# p1dc-001.net
KiCad netlist of a schematic drawn in EAGLE
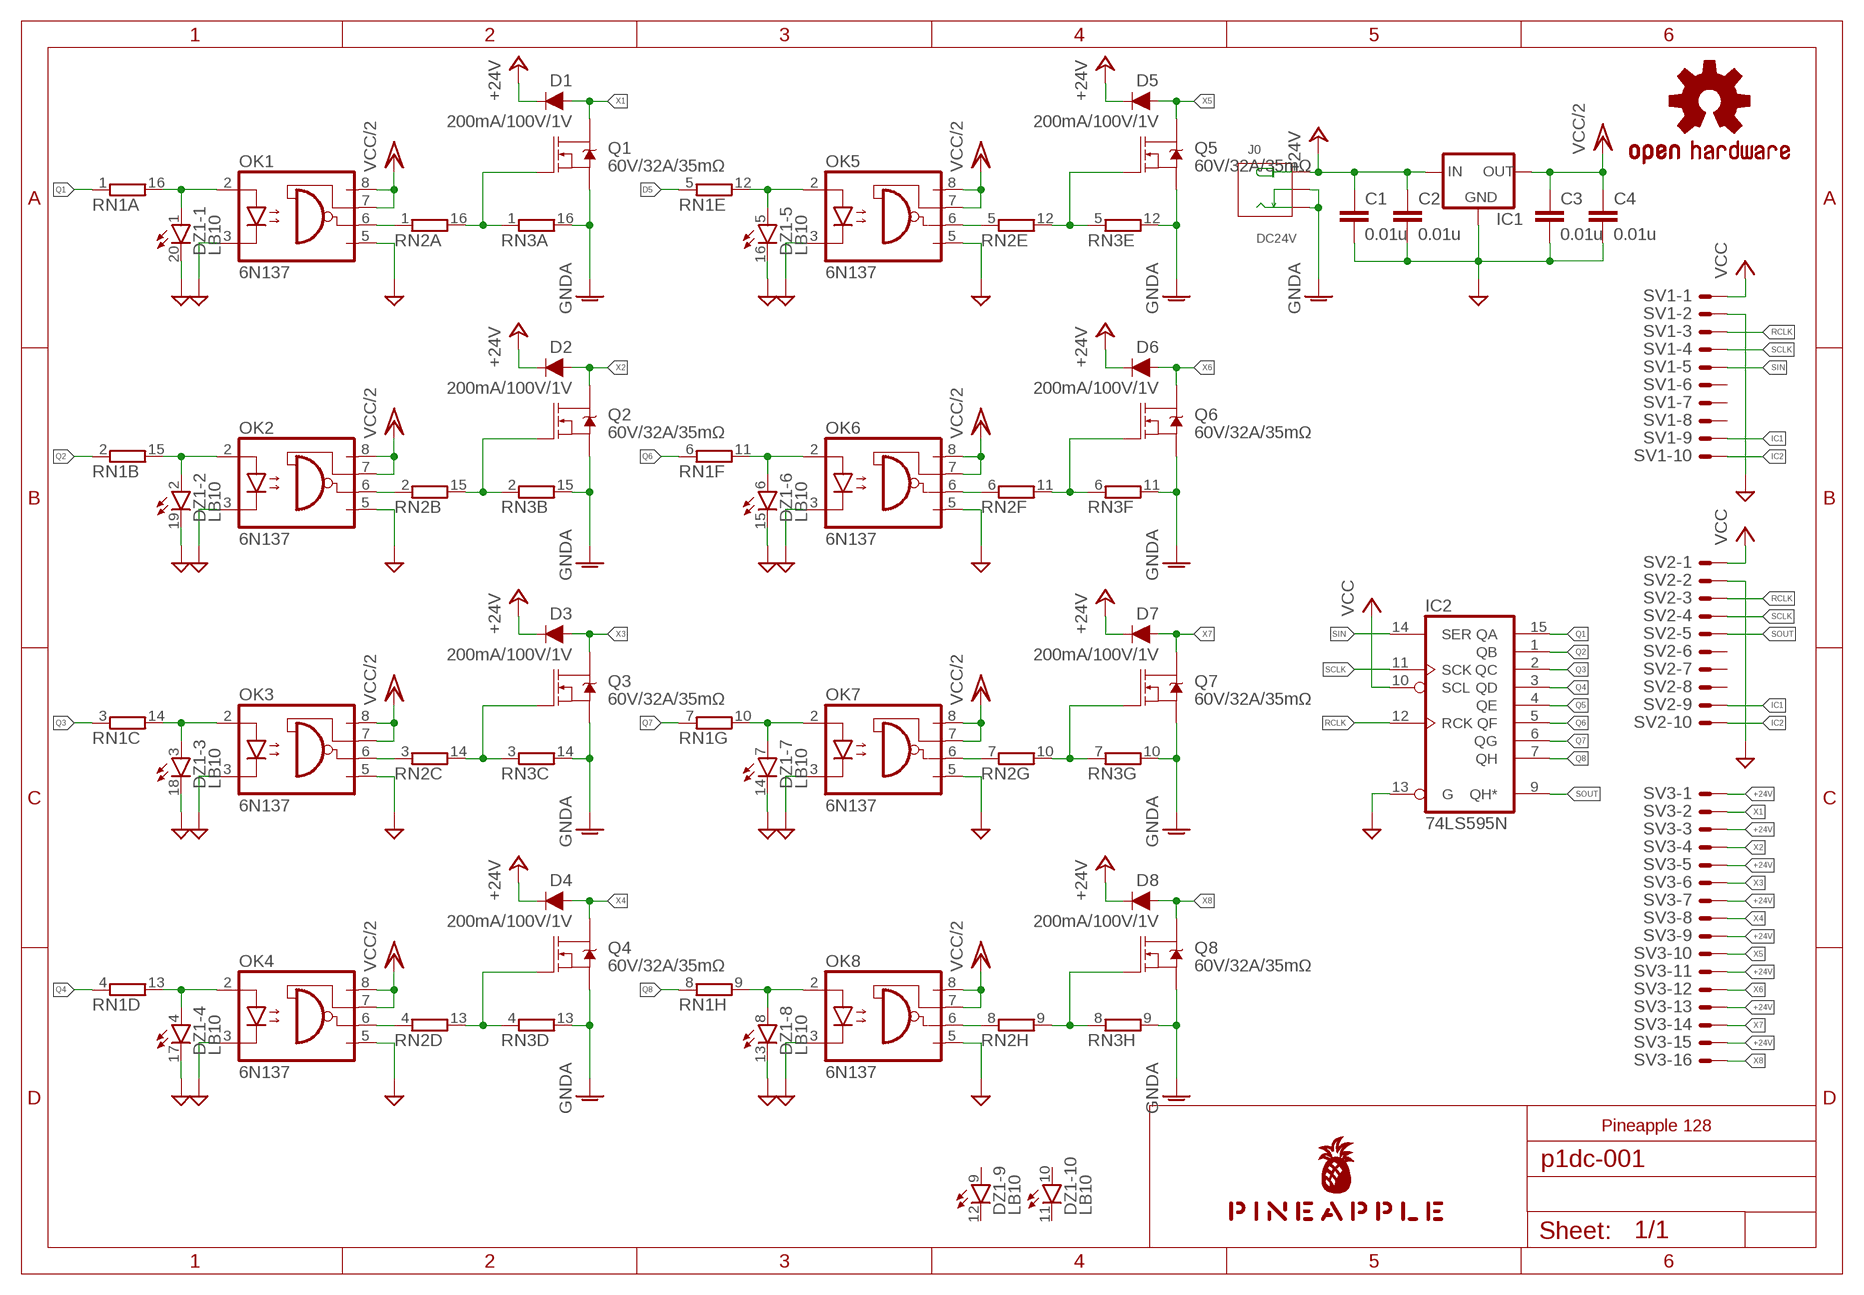
[diagram p0: schematic, sheet 1]

(export (version "E")
  (design (tool "Eeschema 10.0.6"))
  (components
    (comp (ref "C1")
      (value "0.01u")
      (footprint "eagle-import:C025-024X044")
      (libsource (lib "eagle-import") (part "C-EU025-024X044"))
    )
    (comp (ref "C2")
      (value "0.01u")
      (footprint "eagle-import:C025-024X044")
      (libsource (lib "eagle-import") (part "C-EU025-024X044"))
    )
    (comp (ref "C3")
      (value "0.01u")
      (footprint "eagle-import:C025-024X044")
      (libsource (lib "eagle-import") (part "C-EU025-024X044"))
    )
    (comp (ref "C4")
      (value "0.01u")
      (footprint "eagle-import:C025-024X044")
      (libsource (lib "eagle-import") (part "C-EU025-024X044"))
    )
    (comp (ref "D1")
      (value "200mA/100V/1V")
      (footprint "eagle-import:DIODE-1N4148")
      (libsource (lib "eagle-import") (part "DIODE-1N4148"))
    )
    (comp (ref "D2")
      (value "200mA/100V/1V")
      (footprint "eagle-import:DIODE-1N4148")
      (libsource (lib "eagle-import") (part "DIODE-1N4148"))
    )
    (comp (ref "D3")
      (value "200mA/100V/1V")
      (footprint "eagle-import:DIODE-1N4148")
      (libsource (lib "eagle-import") (part "DIODE-1N4148"))
    )
    (comp (ref "D4")
      (value "200mA/100V/1V")
      (footprint "eagle-import:DIODE-1N4148")
      (libsource (lib "eagle-import") (part "DIODE-1N4148"))
    )
    (comp (ref "D5")
      (value "200mA/100V/1V")
      (footprint "eagle-import:DIODE-1N4148")
      (libsource (lib "eagle-import") (part "DIODE-1N4148"))
    )
    (comp (ref "D6")
      (value "200mA/100V/1V")
      (footprint "eagle-import:DIODE-1N4148")
      (libsource (lib "eagle-import") (part "DIODE-1N4148"))
    )
    (comp (ref "D7")
      (value "200mA/100V/1V")
      (footprint "eagle-import:DIODE-1N4148")
      (libsource (lib "eagle-import") (part "DIODE-1N4148"))
    )
    (comp (ref "D8")
      (value "200mA/100V/1V")
      (footprint "eagle-import:DIODE-1N4148")
      (libsource (lib "eagle-import") (part "DIODE-1N4148"))
    )
    (comp (ref "DZ1")
      (value "LB10")
      (footprint "eagle-import:LB10")
      (libsource (lib "eagle-import") (part "LB10"))
    )
    (comp (ref "IC1")
      (value "78XXS")
      (footprint "eagle-import:78XXS")
      (libsource (lib "eagle-import") (part "78XXS"))
    )
    (comp (ref "IC2")
      (value "74LS595N")
      (footprint "eagle-import:DIL16")
      (libsource (lib "eagle-import") (part "74595NLS"))
    )
    (comp (ref "J0")
      (value "DC24V")
      (footprint "eagle-import:3P-L14.2_W11.0_H9.0MM")
      (libsource (lib "eagle-import") (part "JACK-DC-005'DC-005'"))
    )
    (comp (ref "LOGO1")
      (value "OSHW-LOGOS-COPPER")
      (footprint "eagle-import:OSHW-LOGO-S_COPPER")
      (libsource (lib "eagle-import") (part "OSHW-LOGOS-COPPER"))
    )
    (comp (ref "OK1")
      (value "6N137")
      (footprint "eagle-import:DIL08")
      (libsource (lib "eagle-import") (part "6N137"))
    )
    (comp (ref "OK2")
      (value "6N137")
      (footprint "eagle-import:DIL08")
      (libsource (lib "eagle-import") (part "6N137"))
    )
    (comp (ref "OK3")
      (value "6N137")
      (footprint "eagle-import:DIL08")
      (libsource (lib "eagle-import") (part "6N137"))
    )
    (comp (ref "OK4")
      (value "6N137")
      (footprint "eagle-import:DIL08")
      (libsource (lib "eagle-import") (part "6N137"))
    )
    (comp (ref "OK5")
      (value "6N137")
      (footprint "eagle-import:DIL08")
      (libsource (lib "eagle-import") (part "6N137"))
    )
    (comp (ref "OK6")
      (value "6N137")
      (footprint "eagle-import:DIL08")
      (libsource (lib "eagle-import") (part "6N137"))
    )
    (comp (ref "OK7")
      (value "6N137")
      (footprint "eagle-import:DIL08")
      (libsource (lib "eagle-import") (part "6N137"))
    )
    (comp (ref "OK8")
      (value "6N137")
      (footprint "eagle-import:DIL08")
      (libsource (lib "eagle-import") (part "6N137"))
    )
    (comp (ref "Q1")
      (value "60V/32A/35mΩ")
      (footprint "eagle-import:TO220V")
      (libsource (lib "eagle-import") (part "MOSFET-NCH-FQP30N06L"))
    )
    (comp (ref "Q2")
      (value "60V/32A/35mΩ")
      (footprint "eagle-import:TO220V")
      (libsource (lib "eagle-import") (part "MOSFET-NCH-FQP30N06L"))
    )
    (comp (ref "Q3")
      (value "60V/32A/35mΩ")
      (footprint "eagle-import:TO220V")
      (libsource (lib "eagle-import") (part "MOSFET-NCH-FQP30N06L"))
    )
    (comp (ref "Q4")
      (value "60V/32A/35mΩ")
      (footprint "eagle-import:TO220V")
      (libsource (lib "eagle-import") (part "MOSFET-NCH-FQP30N06L"))
    )
    (comp (ref "Q5")
      (value "60V/32A/35mΩ")
      (footprint "eagle-import:TO220V")
      (libsource (lib "eagle-import") (part "MOSFET-NCH-FQP30N06L"))
    )
    (comp (ref "Q6")
      (value "60V/32A/35mΩ")
      (footprint "eagle-import:TO220V")
      (libsource (lib "eagle-import") (part "MOSFET-NCH-FQP30N06L"))
    )
    (comp (ref "Q7")
      (value "60V/32A/35mΩ")
      (footprint "eagle-import:TO220V")
      (libsource (lib "eagle-import") (part "MOSFET-NCH-FQP30N06L"))
    )
    (comp (ref "Q8")
      (value "60V/32A/35mΩ")
      (footprint "eagle-import:TO220V")
      (libsource (lib "eagle-import") (part "MOSFET-NCH-FQP30N06L"))
    )
    (comp (ref "RN1")
      (value "8R-N")
      (footprint "eagle-import:DIL16")
      (libsource (lib "eagle-import") (part "8R-N"))
    )
    (comp (ref "RN2")
      (value "8R-N")
      (footprint "eagle-import:DIL16")
      (libsource (lib "eagle-import") (part "8R-N"))
    )
    (comp (ref "RN3")
      (value "8R-N")
      (footprint "eagle-import:DIL16")
      (libsource (lib "eagle-import") (part "8R-N"))
    )
    (comp (ref "SV1")
      (value "ML10LE")
      (footprint "eagle-import:ML10L")
      (libsource (lib "eagle-import") (part "ML10LE"))
    )
    (comp (ref "SV2")
      (value "ML10LE")
      (footprint "eagle-import:ML10L")
      (libsource (lib "eagle-import") (part "ML10LE"))
    )
    (comp (ref "SV3")
      (value "ML16LE")
      (footprint "eagle-import:ML16L")
      (libsource (lib "eagle-import") (part "ML16LE"))
    )
    (comp (ref "U$1")
      (value "PINEAPPLE450_SILK")
      (footprint "eagle-import:PINEAPPLE450_SILK")
      (libsource (lib "eagle-import") (part "PINEAPPLE450_SILK"))
    )
  )
  (nets
    (net (code "1") (name "+24V") (class "Default")
      (node (ref "C1") (pin "1") (pinfunction "1_1") (pintype "passive"))
      (node (ref "C2") (pin "1") (pinfunction "1_1") (pintype "passive"))
      (node (ref "D1") (pin "C") (pinfunction "C_C") (pintype "passive"))
      (node (ref "D2") (pin "C") (pinfunction "C_C") (pintype "passive"))
      (node (ref "D3") (pin "C") (pinfunction "C_C") (pintype "passive"))
      (node (ref "D4") (pin "C") (pinfunction "C_C") (pintype "passive"))
      (node (ref "D5") (pin "C") (pinfunction "C_C") (pintype "passive"))
      (node (ref "D6") (pin "C") (pinfunction "C_C") (pintype "passive"))
      (node (ref "D7") (pin "C") (pinfunction "C_C") (pintype "passive"))
      (node (ref "D8") (pin "C") (pinfunction "C_C") (pintype "passive"))
      (node (ref "IC1") (pin "IN") (pinfunction "IN_IN") (pintype "input"))
      (node (ref "J0") (pin "+") (pinfunction "+_+") (pintype "bidirectional"))
      (node (ref "SV3") (pin "1") (pinfunction "S_1") (pintype "passive"))
      (node (ref "SV3") (pin "11") (pinfunction "S_11") (pintype "passive"))
      (node (ref "SV3") (pin "13") (pinfunction "S_13") (pintype "passive"))
      (node (ref "SV3") (pin "15") (pinfunction "S_15") (pintype "passive"))
      (node (ref "SV3") (pin "3") (pinfunction "S_3") (pintype "passive"))
      (node (ref "SV3") (pin "5") (pinfunction "S_5") (pintype "passive"))
      (node (ref "SV3") (pin "7") (pinfunction "S_7") (pintype "passive"))
      (node (ref "SV3") (pin "9") (pinfunction "S_9") (pintype "passive"))
    )
    (net (code "2") (name "D5") (class "Default")
      (node (ref "RN1") (pin "5") (pinfunction "1_5") (pintype "passive"))
    )
    (net (code "3") (name "GND") (class "Default")
      (node (ref "C1") (pin "2") (pinfunction "2_2") (pintype "passive"))
      (node (ref "C2") (pin "2") (pinfunction "2_2") (pintype "passive"))
      (node (ref "C3") (pin "2") (pinfunction "2_2") (pintype "passive"))
      (node (ref "C4") (pin "2") (pinfunction "2_2") (pintype "passive"))
      (node (ref "DZ1") (pin "13") (pinfunction "C_13") (pintype "passive"))
      (node (ref "DZ1") (pin "14") (pinfunction "C_14") (pintype "passive"))
      (node (ref "DZ1") (pin "15") (pinfunction "C_15") (pintype "passive"))
      (node (ref "DZ1") (pin "16") (pinfunction "C_16") (pintype "passive"))
      (node (ref "DZ1") (pin "17") (pinfunction "C_17") (pintype "passive"))
      (node (ref "DZ1") (pin "18") (pinfunction "C_18") (pintype "passive"))
      (node (ref "DZ1") (pin "19") (pinfunction "C_19") (pintype "passive"))
      (node (ref "DZ1") (pin "20") (pinfunction "C_20") (pintype "passive"))
      (node (ref "IC1") (pin "GND") (pinfunction "GND_GND") (pintype "input"))
      (node (ref "IC2") (pin "13") (pinfunction "G_13") (pintype "input"))
      (node (ref "OK1") (pin "3") (pinfunction "C_3") (pintype "passive"))
      (node (ref "OK1") (pin "5") (pinfunction "GND_5") (pintype "passive"))
      (node (ref "OK2") (pin "3") (pinfunction "C_3") (pintype "passive"))
      (node (ref "OK2") (pin "5") (pinfunction "GND_5") (pintype "passive"))
      (node (ref "OK3") (pin "3") (pinfunction "C_3") (pintype "passive"))
      (node (ref "OK3") (pin "5") (pinfunction "GND_5") (pintype "passive"))
      (node (ref "OK4") (pin "3") (pinfunction "C_3") (pintype "passive"))
      (node (ref "OK4") (pin "5") (pinfunction "GND_5") (pintype "passive"))
      (node (ref "OK5") (pin "3") (pinfunction "C_3") (pintype "passive"))
      (node (ref "OK5") (pin "5") (pinfunction "GND_5") (pintype "passive"))
      (node (ref "OK6") (pin "3") (pinfunction "C_3") (pintype "passive"))
      (node (ref "OK6") (pin "5") (pinfunction "GND_5") (pintype "passive"))
      (node (ref "OK7") (pin "3") (pinfunction "C_3") (pintype "passive"))
      (node (ref "OK7") (pin "5") (pinfunction "GND_5") (pintype "passive"))
      (node (ref "OK8") (pin "3") (pinfunction "C_3") (pintype "passive"))
      (node (ref "OK8") (pin "5") (pinfunction "GND_5") (pintype "passive"))
      (node (ref "SV1") (pin "2") (pinfunction "S_2") (pintype "passive"))
      (node (ref "SV2") (pin "2") (pinfunction "S_2") (pintype "passive"))
    )
    (net (code "4") (name "GNDA") (class "Default")
      (node (ref "J0") (pin "-1") (pinfunction "-_-1") (pintype "bidirectional"))
      (node (ref "J0") (pin "-2") (pinfunction "CDN_-2") (pintype "bidirectional"))
      (node (ref "Q1") (pin "3") (pinfunction "S_3") (pintype "bidirectional"))
      (node (ref "Q2") (pin "3") (pinfunction "S_3") (pintype "bidirectional"))
      (node (ref "Q3") (pin "3") (pinfunction "S_3") (pintype "bidirectional"))
      (node (ref "Q4") (pin "3") (pinfunction "S_3") (pintype "bidirectional"))
      (node (ref "Q5") (pin "3") (pinfunction "S_3") (pintype "bidirectional"))
      (node (ref "Q6") (pin "3") (pinfunction "S_3") (pintype "bidirectional"))
      (node (ref "Q7") (pin "3") (pinfunction "S_3") (pintype "bidirectional"))
      (node (ref "Q8") (pin "3") (pinfunction "S_3") (pintype "bidirectional"))
      (node (ref "RN3") (pin "10") (pinfunction "2_10") (pintype "passive"))
      (node (ref "RN3") (pin "11") (pinfunction "2_11") (pintype "passive"))
      (node (ref "RN3") (pin "12") (pinfunction "2_12") (pintype "passive"))
      (node (ref "RN3") (pin "13") (pinfunction "2_13") (pintype "passive"))
      (node (ref "RN3") (pin "14") (pinfunction "2_14") (pintype "passive"))
      (node (ref "RN3") (pin "15") (pinfunction "2_15") (pintype "passive"))
      (node (ref "RN3") (pin "16") (pinfunction "2_16") (pintype "passive"))
      (node (ref "RN3") (pin "9") (pinfunction "2_9") (pintype "passive"))
    )
    (net (code "5") (name "IC1") (class "Default")
      (node (ref "SV1") (pin "9") (pinfunction "S_9") (pintype "passive"))
      (node (ref "SV2") (pin "9") (pinfunction "S_9") (pintype "passive"))
    )
    (net (code "6") (name "IC2") (class "Default")
      (node (ref "SV1") (pin "10") (pinfunction "S_10") (pintype "passive"))
      (node (ref "SV2") (pin "10") (pinfunction "S_10") (pintype "passive"))
    )
    (net (code "7") (name "Net-(DZ1A-A)") (class "Default")
      (node (ref "DZ1") (pin "1") (pinfunction "A_1") (pintype "passive"))
      (node (ref "OK1") (pin "2") (pinfunction "A_2") (pintype "passive"))
      (node (ref "RN1") (pin "16") (pinfunction "2_16") (pintype "passive"))
    )
    (net (code "8") (name "Net-(DZ1C-A)") (class "Default")
      (node (ref "DZ1") (pin "2") (pinfunction "A_2") (pintype "passive"))
      (node (ref "OK2") (pin "2") (pinfunction "A_2") (pintype "passive"))
      (node (ref "RN1") (pin "15") (pinfunction "2_15") (pintype "passive"))
    )
    (net (code "9") (name "Net-(DZ1D-A)") (class "Default")
      (node (ref "DZ1") (pin "3") (pinfunction "A_3") (pintype "passive"))
      (node (ref "OK3") (pin "2") (pinfunction "A_2") (pintype "passive"))
      (node (ref "RN1") (pin "14") (pinfunction "2_14") (pintype "passive"))
    )
    (net (code "10") (name "Net-(DZ1E-A)") (class "Default")
      (node (ref "DZ1") (pin "4") (pinfunction "A_4") (pintype "passive"))
      (node (ref "OK4") (pin "2") (pinfunction "A_2") (pintype "passive"))
      (node (ref "RN1") (pin "13") (pinfunction "2_13") (pintype "passive"))
    )
    (net (code "11") (name "Net-(DZ1F-A)") (class "Default")
      (node (ref "DZ1") (pin "5") (pinfunction "A_5") (pintype "passive"))
      (node (ref "OK5") (pin "2") (pinfunction "A_2") (pintype "passive"))
      (node (ref "RN1") (pin "12") (pinfunction "2_12") (pintype "passive"))
    )
    (net (code "12") (name "Net-(DZ1G-A)") (class "Default")
      (node (ref "DZ1") (pin "6") (pinfunction "A_6") (pintype "passive"))
      (node (ref "OK6") (pin "2") (pinfunction "A_2") (pintype "passive"))
      (node (ref "RN1") (pin "11") (pinfunction "2_11") (pintype "passive"))
    )
    (net (code "13") (name "Net-(DZ1H-A)") (class "Default")
      (node (ref "DZ1") (pin "7") (pinfunction "A_7") (pintype "passive"))
      (node (ref "OK7") (pin "2") (pinfunction "A_2") (pintype "passive"))
      (node (ref "RN1") (pin "10") (pinfunction "2_10") (pintype "passive"))
    )
    (net (code "14") (name "Net-(DZ1I-A)") (class "Default")
      (node (ref "DZ1") (pin "8") (pinfunction "A_8") (pintype "passive"))
      (node (ref "OK8") (pin "2") (pinfunction "A_2") (pintype "passive"))
      (node (ref "RN1") (pin "9") (pinfunction "2_9") (pintype "passive"))
    )
    (net (code "15") (name "Net-(OK1-VO)") (class "Default")
      (node (ref "OK1") (pin "6") (pinfunction "VO_6") (pintype "passive"))
      (node (ref "RN2") (pin "1") (pinfunction "1_1") (pintype "passive"))
    )
    (net (code "16") (name "Net-(OK2-VO)") (class "Default")
      (node (ref "OK2") (pin "6") (pinfunction "VO_6") (pintype "passive"))
      (node (ref "RN2") (pin "2") (pinfunction "1_2") (pintype "passive"))
    )
    (net (code "17") (name "Net-(OK3-VO)") (class "Default")
      (node (ref "OK3") (pin "6") (pinfunction "VO_6") (pintype "passive"))
      (node (ref "RN2") (pin "3") (pinfunction "1_3") (pintype "passive"))
    )
    (net (code "18") (name "Net-(OK4-VO)") (class "Default")
      (node (ref "OK4") (pin "6") (pinfunction "VO_6") (pintype "passive"))
      (node (ref "RN2") (pin "4") (pinfunction "1_4") (pintype "passive"))
    )
    (net (code "19") (name "Net-(OK5-VO)") (class "Default")
      (node (ref "OK5") (pin "6") (pinfunction "VO_6") (pintype "passive"))
      (node (ref "RN2") (pin "5") (pinfunction "1_5") (pintype "passive"))
    )
    (net (code "20") (name "Net-(OK6-VO)") (class "Default")
      (node (ref "OK6") (pin "6") (pinfunction "VO_6") (pintype "passive"))
      (node (ref "RN2") (pin "6") (pinfunction "1_6") (pintype "passive"))
    )
    (net (code "21") (name "Net-(OK7-VO)") (class "Default")
      (node (ref "OK7") (pin "6") (pinfunction "VO_6") (pintype "passive"))
      (node (ref "RN2") (pin "7") (pinfunction "1_7") (pintype "passive"))
    )
    (net (code "22") (name "Net-(OK8-VO)") (class "Default")
      (node (ref "OK8") (pin "6") (pinfunction "VO_6") (pintype "passive"))
      (node (ref "RN2") (pin "8") (pinfunction "1_8") (pintype "passive"))
    )
    (net (code "23") (name "Net-(Q1-G)") (class "Default")
      (node (ref "Q1") (pin "1") (pinfunction "G_1") (pintype "bidirectional"))
      (node (ref "RN2") (pin "16") (pinfunction "2_16") (pintype "passive"))
      (node (ref "RN3") (pin "1") (pinfunction "1_1") (pintype "passive"))
    )
    (net (code "24") (name "Net-(Q2-G)") (class "Default")
      (node (ref "Q2") (pin "1") (pinfunction "G_1") (pintype "bidirectional"))
      (node (ref "RN2") (pin "15") (pinfunction "2_15") (pintype "passive"))
      (node (ref "RN3") (pin "2") (pinfunction "1_2") (pintype "passive"))
    )
    (net (code "25") (name "Net-(Q3-G)") (class "Default")
      (node (ref "Q3") (pin "1") (pinfunction "G_1") (pintype "bidirectional"))
      (node (ref "RN2") (pin "14") (pinfunction "2_14") (pintype "passive"))
      (node (ref "RN3") (pin "3") (pinfunction "1_3") (pintype "passive"))
    )
    (net (code "26") (name "Net-(Q4-G)") (class "Default")
      (node (ref "Q4") (pin "1") (pinfunction "G_1") (pintype "bidirectional"))
      (node (ref "RN2") (pin "13") (pinfunction "2_13") (pintype "passive"))
      (node (ref "RN3") (pin "4") (pinfunction "1_4") (pintype "passive"))
    )
    (net (code "27") (name "Net-(Q5-G)") (class "Default")
      (node (ref "Q5") (pin "1") (pinfunction "G_1") (pintype "bidirectional"))
      (node (ref "RN2") (pin "12") (pinfunction "2_12") (pintype "passive"))
      (node (ref "RN3") (pin "5") (pinfunction "1_5") (pintype "passive"))
    )
    (net (code "28") (name "Net-(Q6-G)") (class "Default")
      (node (ref "Q6") (pin "1") (pinfunction "G_1") (pintype "bidirectional"))
      (node (ref "RN2") (pin "11") (pinfunction "2_11") (pintype "passive"))
      (node (ref "RN3") (pin "6") (pinfunction "1_6") (pintype "passive"))
    )
    (net (code "29") (name "Net-(Q7-G)") (class "Default")
      (node (ref "Q7") (pin "1") (pinfunction "G_1") (pintype "bidirectional"))
      (node (ref "RN2") (pin "10") (pinfunction "2_10") (pintype "passive"))
      (node (ref "RN3") (pin "7") (pinfunction "1_7") (pintype "passive"))
    )
    (net (code "30") (name "Net-(Q8-G)") (class "Default")
      (node (ref "Q8") (pin "1") (pinfunction "G_1") (pintype "bidirectional"))
      (node (ref "RN2") (pin "9") (pinfunction "2_9") (pintype "passive"))
      (node (ref "RN3") (pin "8") (pinfunction "1_8") (pintype "passive"))
    )
    (net (code "31") (name "Q1") (class "Default")
      (node (ref "IC2") (pin "15") (pinfunction "QA_15") (pintype "tri_state"))
      (node (ref "RN1") (pin "1") (pinfunction "1_1") (pintype "passive"))
    )
    (net (code "32") (name "Q2") (class "Default")
      (node (ref "IC2") (pin "1") (pinfunction "QB_1") (pintype "tri_state"))
      (node (ref "RN1") (pin "2") (pinfunction "1_2") (pintype "passive"))
    )
    (net (code "33") (name "Q3") (class "Default")
      (node (ref "IC2") (pin "2") (pinfunction "QC_2") (pintype "tri_state"))
      (node (ref "RN1") (pin "3") (pinfunction "1_3") (pintype "passive"))
    )
    (net (code "34") (name "Q4") (class "Default")
      (node (ref "IC2") (pin "3") (pinfunction "QD_3") (pintype "tri_state"))
      (node (ref "RN1") (pin "4") (pinfunction "1_4") (pintype "passive"))
    )
    (net (code "35") (name "Q5") (class "Default")
      (node (ref "IC2") (pin "4") (pinfunction "QE_4") (pintype "tri_state"))
    )
    (net (code "36") (name "Q6") (class "Default")
      (node (ref "IC2") (pin "5") (pinfunction "QF_5") (pintype "tri_state"))
      (node (ref "RN1") (pin "6") (pinfunction "1_6") (pintype "passive"))
    )
    (net (code "37") (name "Q7") (class "Default")
      (node (ref "IC2") (pin "6") (pinfunction "QG_6") (pintype "tri_state"))
      (node (ref "RN1") (pin "7") (pinfunction "1_7") (pintype "passive"))
    )
    (net (code "38") (name "Q8") (class "Default")
      (node (ref "IC2") (pin "7") (pinfunction "QH_7") (pintype "tri_state"))
      (node (ref "RN1") (pin "8") (pinfunction "1_8") (pintype "passive"))
    )
    (net (code "39") (name "RCLK") (class "Default")
      (node (ref "IC2") (pin "12") (pinfunction "RCK_12") (pintype "input"))
      (node (ref "SV1") (pin "3") (pinfunction "S_3") (pintype "passive"))
      (node (ref "SV2") (pin "3") (pinfunction "S_3") (pintype "passive"))
    )
    (net (code "40") (name "SCLK") (class "Default")
      (node (ref "IC2") (pin "11") (pinfunction "SCK_11") (pintype "input"))
      (node (ref "SV1") (pin "4") (pinfunction "S_4") (pintype "passive"))
      (node (ref "SV2") (pin "4") (pinfunction "S_4") (pintype "passive"))
    )
    (net (code "41") (name "SIN") (class "Default")
      (node (ref "IC2") (pin "14") (pinfunction "SER_14") (pintype "input"))
      (node (ref "SV1") (pin "5") (pinfunction "S_5") (pintype "passive"))
    )
    (net (code "42") (name "SOUT") (class "Default")
      (node (ref "IC2") (pin "9") (pinfunction "QH*_9") (pintype "tri_state"))
      (node (ref "SV2") (pin "5") (pinfunction "S_5") (pintype "passive"))
    )
    (net (code "43") (name "VCC") (class "Default")
      (node (ref "IC2") (pin "10") (pinfunction "SCL_10") (pintype "input"))
      (node (ref "SV1") (pin "1") (pinfunction "S_1") (pintype "passive"))
      (node (ref "SV2") (pin "1") (pinfunction "S_1") (pintype "passive"))
    )
    (net (code "44") (name "VCC{slash}2") (class "Default")
      (node (ref "C3") (pin "1") (pinfunction "1_1") (pintype "passive"))
      (node (ref "C4") (pin "1") (pinfunction "1_1") (pintype "passive"))
      (node (ref "IC1") (pin "OUT") (pinfunction "OUT_OUT") (pintype "passive"))
      (node (ref "OK1") (pin "7") (pinfunction "VE_7") (pintype "passive"))
      (node (ref "OK1") (pin "8") (pinfunction "VCC_8") (pintype "passive"))
      (node (ref "OK2") (pin "7") (pinfunction "VE_7") (pintype "passive"))
      (node (ref "OK2") (pin "8") (pinfunction "VCC_8") (pintype "passive"))
      (node (ref "OK3") (pin "7") (pinfunction "VE_7") (pintype "passive"))
      (node (ref "OK3") (pin "8") (pinfunction "VCC_8") (pintype "passive"))
      (node (ref "OK4") (pin "7") (pinfunction "VE_7") (pintype "passive"))
      (node (ref "OK4") (pin "8") (pinfunction "VCC_8") (pintype "passive"))
      (node (ref "OK5") (pin "7") (pinfunction "VE_7") (pintype "passive"))
      (node (ref "OK5") (pin "8") (pinfunction "VCC_8") (pintype "passive"))
      (node (ref "OK6") (pin "7") (pinfunction "VE_7") (pintype "passive"))
      (node (ref "OK6") (pin "8") (pinfunction "VCC_8") (pintype "passive"))
      (node (ref "OK7") (pin "7") (pinfunction "VE_7") (pintype "passive"))
      (node (ref "OK7") (pin "8") (pinfunction "VCC_8") (pintype "passive"))
      (node (ref "OK8") (pin "7") (pinfunction "VE_7") (pintype "passive"))
      (node (ref "OK8") (pin "8") (pinfunction "VCC_8") (pintype "passive"))
    )
    (net (code "45") (name "X1") (class "Default")
      (node (ref "D1") (pin "A") (pinfunction "A_A") (pintype "passive"))
      (node (ref "Q1") (pin "2") (pinfunction "D_2") (pintype "bidirectional"))
      (node (ref "SV3") (pin "2") (pinfunction "S_2") (pintype "passive"))
    )
    (net (code "46") (name "X2") (class "Default")
      (node (ref "D2") (pin "A") (pinfunction "A_A") (pintype "passive"))
      (node (ref "Q2") (pin "2") (pinfunction "D_2") (pintype "bidirectional"))
      (node (ref "SV3") (pin "4") (pinfunction "S_4") (pintype "passive"))
    )
    (net (code "47") (name "X3") (class "Default")
      (node (ref "D3") (pin "A") (pinfunction "A_A") (pintype "passive"))
      (node (ref "Q3") (pin "2") (pinfunction "D_2") (pintype "bidirectional"))
      (node (ref "SV3") (pin "6") (pinfunction "S_6") (pintype "passive"))
    )
    (net (code "48") (name "X4") (class "Default")
      (node (ref "D4") (pin "A") (pinfunction "A_A") (pintype "passive"))
      (node (ref "Q4") (pin "2") (pinfunction "D_2") (pintype "bidirectional"))
      (node (ref "SV3") (pin "8") (pinfunction "S_8") (pintype "passive"))
    )
    (net (code "49") (name "X5") (class "Default")
      (node (ref "D5") (pin "A") (pinfunction "A_A") (pintype "passive"))
      (node (ref "Q5") (pin "2") (pinfunction "D_2") (pintype "bidirectional"))
      (node (ref "SV3") (pin "10") (pinfunction "S_10") (pintype "passive"))
    )
    (net (code "50") (name "X6") (class "Default")
      (node (ref "D6") (pin "A") (pinfunction "A_A") (pintype "passive"))
      (node (ref "Q6") (pin "2") (pinfunction "D_2") (pintype "bidirectional"))
      (node (ref "SV3") (pin "12") (pinfunction "S_12") (pintype "passive"))
    )
    (net (code "51") (name "X7") (class "Default")
      (node (ref "D7") (pin "A") (pinfunction "A_A") (pintype "passive"))
      (node (ref "Q7") (pin "2") (pinfunction "D_2") (pintype "bidirectional"))
      (node (ref "SV3") (pin "14") (pinfunction "S_14") (pintype "passive"))
    )
    (net (code "52") (name "X8") (class "Default")
      (node (ref "D8") (pin "A") (pinfunction "A_A") (pintype "passive"))
      (node (ref "Q8") (pin "2") (pinfunction "D_2") (pintype "bidirectional"))
      (node (ref "SV3") (pin "16") (pinfunction "S_16") (pintype "passive"))
    )
    (net (code "53") (name "unconnected-(DZ1B-A-Pad10)") (class "Default")
      (node (ref "DZ1") (pin "10") (pinfunction "A_10") (pintype "passive"))
    )
    (net (code "54") (name "unconnected-(DZ1B-C-Pad11)") (class "Default")
      (node (ref "DZ1") (pin "11") (pinfunction "C_11") (pintype "passive"))
    )
    (net (code "55") (name "unconnected-(DZ1J-A-Pad9)") (class "Default")
      (node (ref "DZ1") (pin "9") (pinfunction "A_9") (pintype "passive"))
    )
    (net (code "56") (name "unconnected-(DZ1J-C-Pad12)") (class "Default")
      (node (ref "DZ1") (pin "12") (pinfunction "C_12") (pintype "passive"))
    )
    (net (code "57") (name "unconnected-(SV1G-S-Pad6)") (class "Default")
      (node (ref "SV1") (pin "6") (pinfunction "S_6") (pintype "passive"))
    )
    (net (code "58") (name "unconnected-(SV1H-S-Pad7)") (class "Default")
      (node (ref "SV1") (pin "7") (pinfunction "S_7") (pintype "passive"))
    )
    (net (code "59") (name "unconnected-(SV1I-S-Pad8)") (class "Default")
      (node (ref "SV1") (pin "8") (pinfunction "S_8") (pintype "passive"))
    )
    (net (code "60") (name "unconnected-(SV2G-S-Pad6)") (class "Default")
      (node (ref "SV2") (pin "6") (pinfunction "S_6") (pintype "passive"))
    )
    (net (code "61") (name "unconnected-(SV2H-S-Pad7)") (class "Default")
      (node (ref "SV2") (pin "7") (pinfunction "S_7") (pintype "passive"))
    )
    (net (code "62") (name "unconnected-(SV2I-S-Pad8)") (class "Default")
      (node (ref "SV2") (pin "8") (pinfunction "S_8") (pintype "passive"))
    )
  )
)
